# child1.net
KiCad netlist of a schematic drawn in Altium Designer
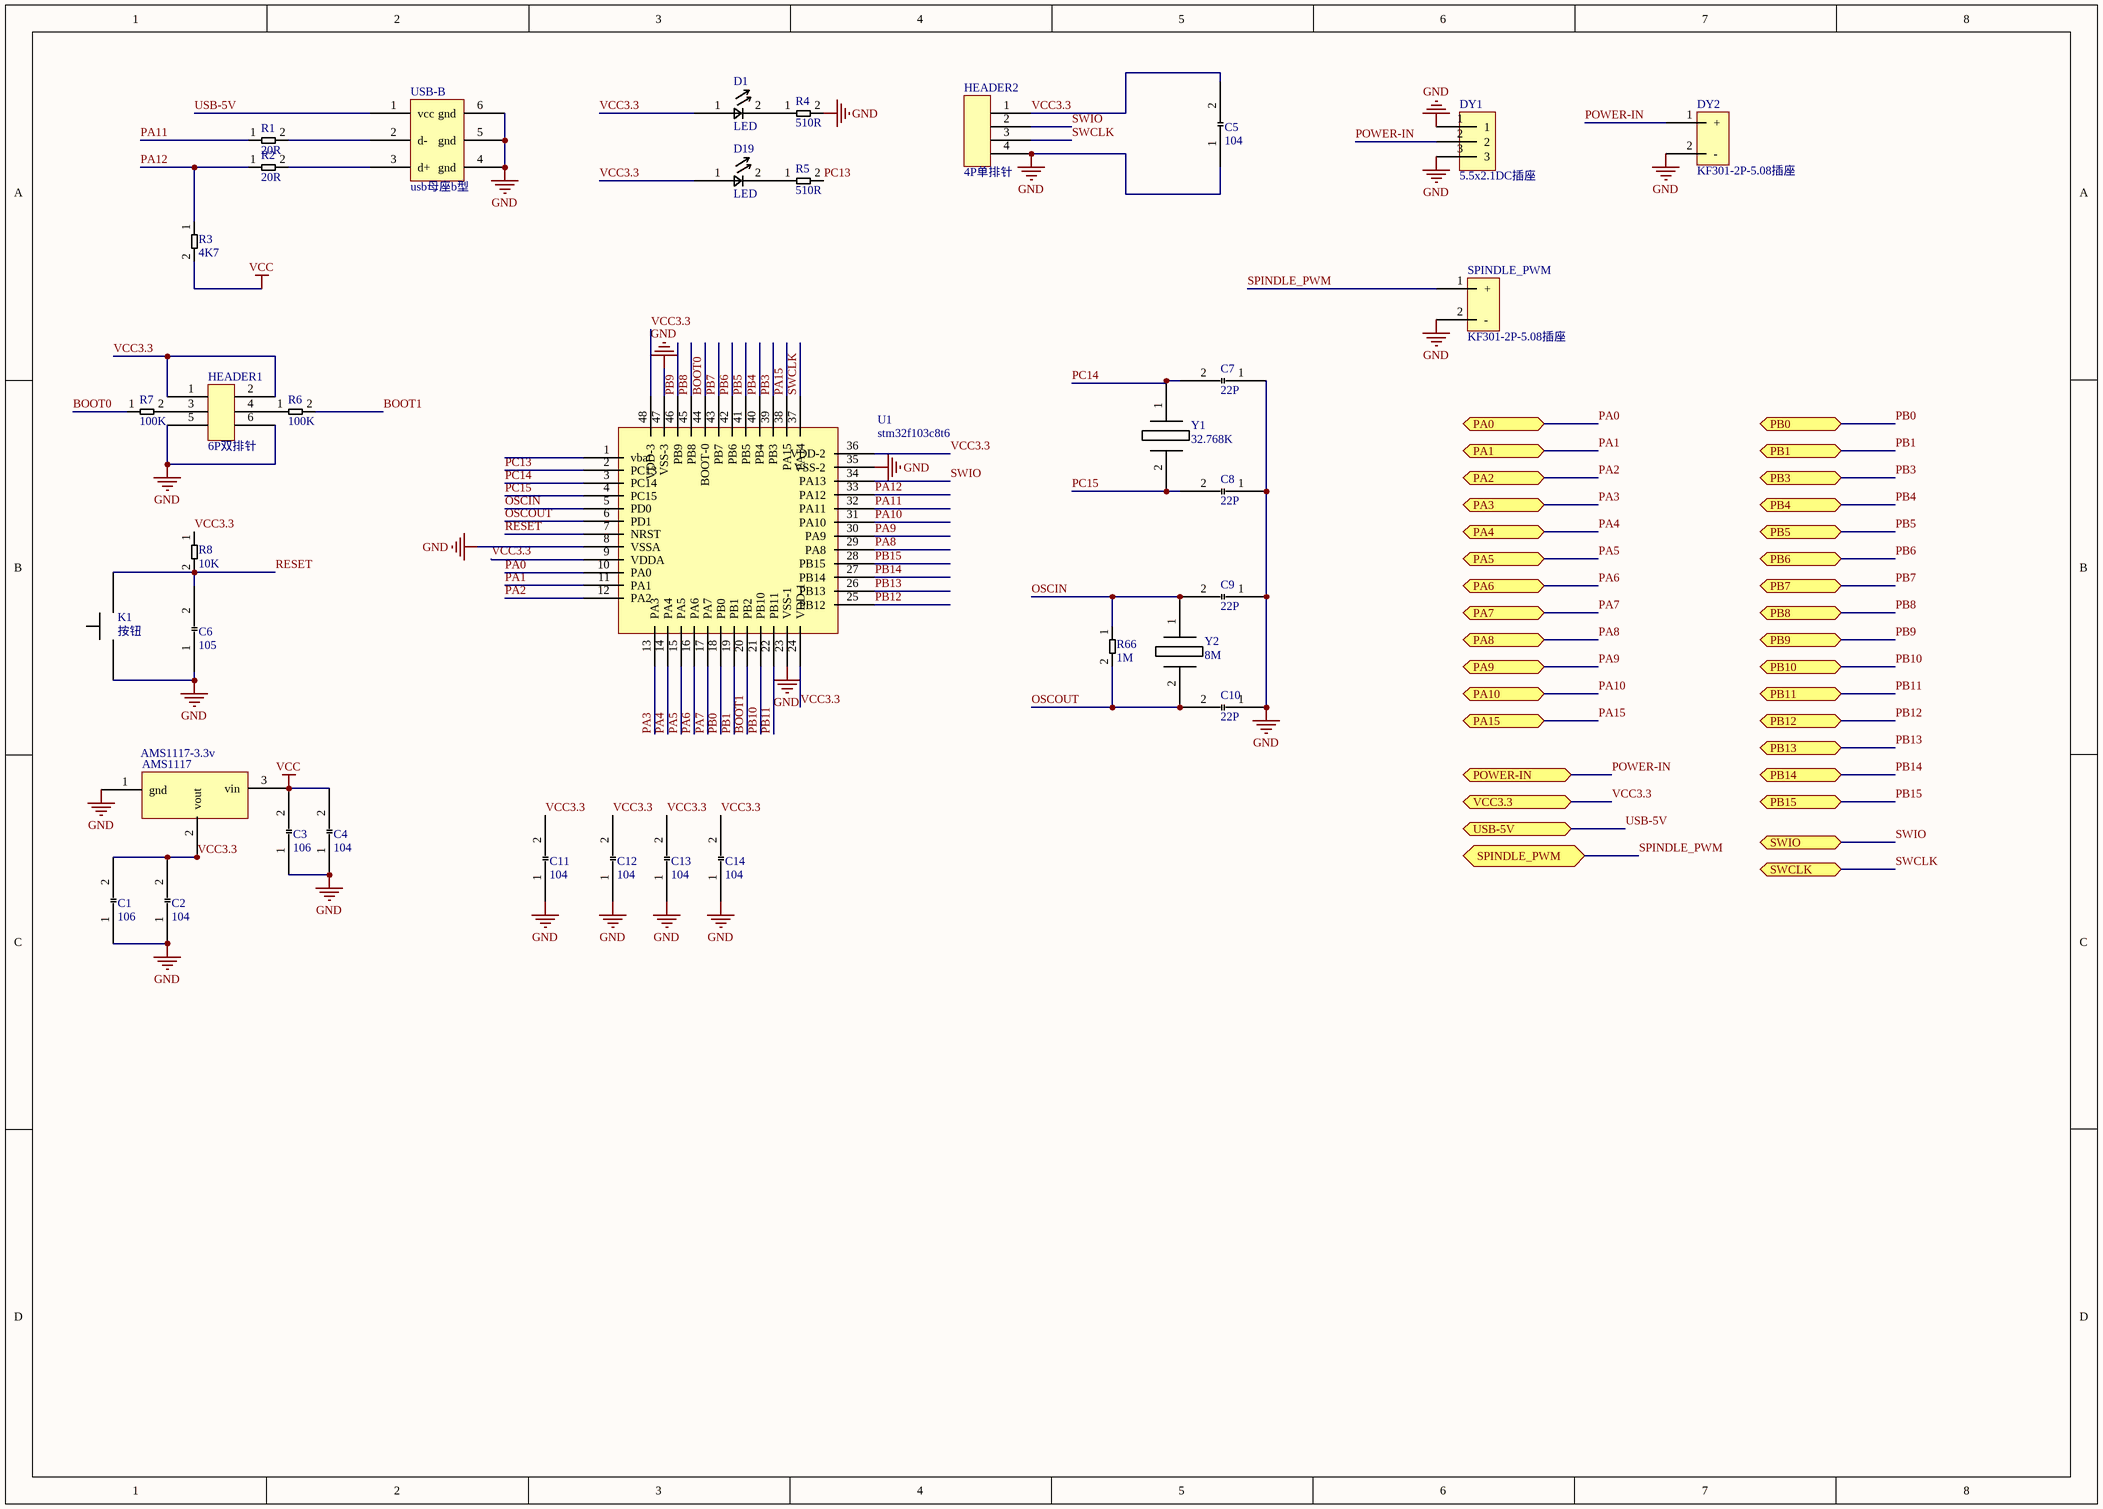
[diagram p0: child1.SchDoc]

(export (version "E")
  (design (tool "Eeschema 10.0.6"))
  (components
    (comp (ref "AMS1117")
      (value "AMS1117-3.3v")
      (footprint "AMS1117-3.3v-sot223")
      (libsource (lib "51单片机") (part "AMS1117-3.3v"))
    )
    (comp (ref "C1") (value "106") (footprint "0805电容") (libsource (lib "51单片机") (part "0805贴片电容")))
    (comp (ref "C2") (value "104") (footprint "0805电容") (libsource (lib "51单片机") (part "0805贴片电容")))
    (comp (ref "C3") (value "106") (footprint "0805电容") (libsource (lib "51单片机") (part "0805贴片电容")))
    (comp (ref "C4") (value "104") (footprint "0805电容") (libsource (lib "51单片机") (part "0805贴片电容")))
    (comp (ref "C5") (value "104") (footprint "0805电容") (libsource (lib "51单片机") (part "0805贴片电容")))
    (comp (ref "C6") (value "105") (footprint "0805电容") (libsource (lib "51单片机") (part "0805贴片电容")))
    (comp (ref "C7") (value "22P") (footprint "0805电容") (libsource (lib "51单片机") (part "0805贴片电容")))
    (comp (ref "C8") (value "22P") (footprint "0805电容") (libsource (lib "51单片机") (part "0805贴片电容")))
    (comp (ref "C9") (value "22P") (footprint "0805电容") (libsource (lib "51单片机") (part "0805贴片电容")))
    (comp (ref "C10") (value "22P") (footprint "0805电容") (libsource (lib "51单片机") (part "0805贴片电容")))
    (comp (ref "C11") (value "104") (footprint "0805电容") (libsource (lib "51单片机") (part "0805贴片电容")))
    (comp (ref "C12") (value "104") (footprint "0805电容") (libsource (lib "51单片机") (part "0805贴片电容")))
    (comp (ref "C13") (value "104") (footprint "0805电容") (libsource (lib "51单片机") (part "0805贴片电容")))
    (comp (ref "C14") (value "104") (footprint "0805电容") (libsource (lib "51单片机") (part "0805贴片电容")))
    (comp (ref "D1") (value "LED") (footprint "0805二极管") (libsource (lib "51单片机") (part "0805贴片发光二极管")))
    (comp (ref "D19") (value "LED") (footprint "0805二极管") (libsource (lib "51单片机") (part "0805贴片发光二极管")))
    (comp (ref "DY1")
      (value "5.5x2.1DC插座")
      (footprint "5.5x2.1DC插座")
      (libsource (lib "51单片机") (part "5.5x2.1DC插座"))
    )
    (comp (ref "DY2")
      (value "KF301-2P-5.08插座")
      (footprint "KF301-2P-5.08插座")
      (libsource (lib "51单片机") (part "KF301-2P-5.08插座"))
    )
    (comp (ref "HEADER1") (value "6P双排针") (footprint "6P双排针") (libsource (lib "51单片机") (part "6P双排针")))
    (comp (ref "HEADER2") (value "4P单排针") (footprint "4p单排针") (libsource (lib "51单片机") (part "4P单排针")))
    (comp (ref "K1") (value "按钮") (footprint "3x4贴片按钮") (libsource (lib "51单片机") (part "3x4贴片按钮")))
    (comp (ref "R1") (value "20R") (footprint "0805电阻") (libsource (lib "51单片机") (part "0805贴片电阻")))
    (comp (ref "R2") (value "20R") (footprint "0805电阻") (libsource (lib "51单片机") (part "0805贴片电阻")))
    (comp (ref "R3") (value "4K7") (footprint "0805电阻") (libsource (lib "51单片机") (part "0805贴片电阻")))
    (comp (ref "R4") (value "510R") (footprint "0805电阻") (libsource (lib "51单片机") (part "0805贴片电阻")))
    (comp (ref "R5") (value "510R") (footprint "0805电阻") (libsource (lib "51单片机") (part "0805贴片电阻")))
    (comp (ref "R6") (value "100K") (footprint "0805电阻") (libsource (lib "51单片机") (part "0805贴片电阻")))
    (comp (ref "R7") (value "100K") (footprint "0805电阻") (libsource (lib "51单片机") (part "0805贴片电阻")))
    (comp (ref "R8") (value "10K") (footprint "0805电阻") (libsource (lib "51单片机") (part "0805贴片电阻")))
    (comp (ref "R66") (value "1M") (footprint "0805电阻") (libsource (lib "51单片机") (part "0805贴片电阻")))
    (comp (ref "SPINDLE_PWM")
      (value "KF301-2P-5.08插座")
      (footprint "KF301-2P-5.08插座")
      (libsource (lib "51单片机") (part "KF301-2P-5.08插座"))
    )
    (comp (ref "U1")
      (value "stm32f103c8t6")
      (footprint "lqfp48")
      (libsource (lib "51单片机") (part "stm32f103c8t6"))
    )
    (comp (ref "USB-B") (value "usb母座b型") (footprint "usb母座b型") (libsource (lib "51单片机") (part "usb母座b型")))
    (comp (ref "Y1") (value "32.768K") (footprint "3.2x1.5晶振") (libsource (lib "51单片机") (part "2脚贴片晶振")))
    (comp (ref "Y2") (value "8M") (footprint "8M贴片晶振") (libsource (lib "51单片机") (part "2脚贴片晶振")))
  )
  (nets
    (net (code "1") (name "/BOOT0") (class "Default")
      (node (ref "R7") (pin "1") (pintype "passive"))
      (node (ref "U1") (pin "44") (pinfunction "BOOT-0_44") (pintype "passive"))
    )
    (net (code "2") (name "/BOOT1") (class "Default")
      (node (ref "R6") (pin "2") (pintype "passive"))
      (node (ref "U1") (pin "20") (pinfunction "PB2_20") (pintype "passive"))
    )
    (net (code "3") (name "/OSCIN") (class "Default")
      (node (ref "C9") (pin "2") (pintype "passive"))
      (node (ref "R66") (pin "1") (pintype "passive"))
      (node (ref "U1") (pin "5") (pinfunction "PD0_5") (pintype "passive"))
      (node (ref "Y2") (pin "1") (pintype "passive"))
    )
    (net (code "4") (name "/OSCOUT") (class "Default")
      (node (ref "C10") (pin "2") (pintype "passive"))
      (node (ref "R66") (pin "2") (pintype "passive"))
      (node (ref "U1") (pin "6") (pinfunction "PD1_6") (pintype "passive"))
      (node (ref "Y2") (pin "2") (pintype "passive"))
    )
    (net (code "5") (name "/PA0") (class "Default")
      (node (ref "U1") (pin "10") (pinfunction "PA0_10") (pintype "passive"))
    )
    (net (code "6") (name "/PA1") (class "Default")
      (node (ref "U1") (pin "11") (pinfunction "PA1_11") (pintype "passive"))
    )
    (net (code "7") (name "/PA2") (class "Default")
      (node (ref "U1") (pin "12") (pinfunction "PA2_12") (pintype "passive"))
    )
    (net (code "8") (name "/PA3") (class "Default")
      (node (ref "U1") (pin "13") (pinfunction "PA3_13") (pintype "passive"))
    )
    (net (code "9") (name "/PA4") (class "Default")
      (node (ref "U1") (pin "14") (pinfunction "PA4_14") (pintype "passive"))
    )
    (net (code "10") (name "/PA5") (class "Default")
      (node (ref "U1") (pin "15") (pinfunction "PA5_15") (pintype "passive"))
    )
    (net (code "11") (name "/PA6") (class "Default")
      (node (ref "U1") (pin "16") (pinfunction "PA6_16") (pintype "passive"))
    )
    (net (code "12") (name "/PA7") (class "Default")
      (node (ref "U1") (pin "17") (pinfunction "PA7_17") (pintype "passive"))
    )
    (net (code "13") (name "/PA8") (class "Default")
      (node (ref "U1") (pin "29") (pinfunction "PA8_29") (pintype "passive"))
    )
    (net (code "14") (name "/PA9") (class "Default")
      (node (ref "U1") (pin "30") (pinfunction "PA9_30") (pintype "passive"))
    )
    (net (code "15") (name "/PA10") (class "Default")
      (node (ref "U1") (pin "31") (pinfunction "PA10_31") (pintype "passive"))
    )
    (net (code "16") (name "/PA11") (class "Default")
      (node (ref "R1") (pin "1") (pintype "passive"))
      (node (ref "U1") (pin "32") (pinfunction "PA11_32") (pintype "passive"))
    )
    (net (code "17") (name "/PA12") (class "Default")
      (node (ref "R2") (pin "1") (pintype "passive"))
      (node (ref "R3") (pin "1") (pintype "passive"))
      (node (ref "U1") (pin "33") (pinfunction "PA12_33") (pintype "passive"))
    )
    (net (code "18") (name "/PA15") (class "Default")
      (node (ref "U1") (pin "38") (pinfunction "PA15_38") (pintype "passive"))
    )
    (net (code "19") (name "/PB0") (class "Default")
      (node (ref "U1") (pin "18") (pinfunction "PB0_18") (pintype "passive"))
    )
    (net (code "20") (name "/PB1") (class "Default")
      (node (ref "U1") (pin "19") (pinfunction "PB1_19") (pintype "passive"))
    )
    (net (code "21") (name "/PB3") (class "Default")
      (node (ref "U1") (pin "39") (pinfunction "PB3_39") (pintype "passive"))
    )
    (net (code "22") (name "/PB4") (class "Default")
      (node (ref "U1") (pin "40") (pinfunction "PB4_40") (pintype "passive"))
    )
    (net (code "23") (name "/PB5") (class "Default")
      (node (ref "U1") (pin "41") (pinfunction "PB5_41") (pintype "passive"))
    )
    (net (code "24") (name "/PB6") (class "Default")
      (node (ref "U1") (pin "42") (pinfunction "PB6_42") (pintype "passive"))
    )
    (net (code "25") (name "/PB7") (class "Default")
      (node (ref "U1") (pin "43") (pinfunction "PB7_43") (pintype "passive"))
    )
    (net (code "26") (name "/PB8") (class "Default")
      (node (ref "U1") (pin "45") (pinfunction "PB8_45") (pintype "passive"))
    )
    (net (code "27") (name "/PB9") (class "Default")
      (node (ref "U1") (pin "46") (pinfunction "PB9_46") (pintype "passive"))
    )
    (net (code "28") (name "/PB10") (class "Default")
      (node (ref "U1") (pin "21") (pinfunction "PB10_21") (pintype "passive"))
    )
    (net (code "29") (name "/PB11") (class "Default")
      (node (ref "U1") (pin "22") (pinfunction "PB11_22") (pintype "passive"))
    )
    (net (code "30") (name "/PB12") (class "Default")
      (node (ref "U1") (pin "25") (pinfunction "PB12_25") (pintype "passive"))
    )
    (net (code "31") (name "/PB13") (class "Default")
      (node (ref "U1") (pin "26") (pinfunction "PB13_26") (pintype "passive"))
    )
    (net (code "32") (name "/PB14") (class "Default")
      (node (ref "U1") (pin "27") (pinfunction "PB14_27") (pintype "passive"))
    )
    (net (code "33") (name "/PB15") (class "Default")
      (node (ref "U1") (pin "28") (pinfunction "PB15_28") (pintype "passive"))
    )
    (net (code "34") (name "/PC13") (class "Default")
      (node (ref "R5") (pin "2") (pintype "passive"))
      (node (ref "U1") (pin "2") (pinfunction "PC13_2") (pintype "passive"))
    )
    (net (code "35") (name "/PC14") (class "Default")
      (node (ref "C7") (pin "2") (pintype "passive"))
      (node (ref "U1") (pin "3") (pinfunction "PC14_3") (pintype "passive"))
      (node (ref "Y1") (pin "1") (pintype "passive"))
    )
    (net (code "36") (name "/PC15") (class "Default")
      (node (ref "C8") (pin "2") (pintype "passive"))
      (node (ref "U1") (pin "4") (pinfunction "PC15_4") (pintype "passive"))
      (node (ref "Y1") (pin "2") (pintype "passive"))
    )
    (net (code "37") (name "/POWER-IN") (class "Default")
      (node (ref "DY1") (pin "2") (pinfunction "2_2") (pintype "passive"))
      (node (ref "DY2") (pin "1") (pinfunction "+_1") (pintype "passive"))
    )
    (net (code "38") (name "/RESET") (class "Default")
      (node (ref "C6") (pin "2") (pintype "passive"))
      (node (ref "K1") (pin "1") (pinfunction "1_1") (pintype "passive"))
      (node (ref "R8") (pin "2") (pintype "passive"))
      (node (ref "U1") (pin "7") (pinfunction "NRST_7") (pintype "passive"))
    )
    (net (code "39") (name "/SPINDLE_PWM") (class "Default")
      (node (ref "SPINDLE_PWM") (pin "1") (pinfunction "+_1") (pintype "passive"))
    )
    (net (code "40") (name "/SWCLK") (class "Default")
      (node (ref "HEADER2") (pin "3") (pintype "passive"))
      (node (ref "U1") (pin "37") (pinfunction "PA14_37") (pintype "passive"))
    )
    (net (code "41") (name "/SWIO") (class "Default")
      (node (ref "HEADER2") (pin "2") (pintype "passive"))
      (node (ref "U1") (pin "34") (pinfunction "PA13_34") (pintype "passive"))
    )
    (net (code "42") (name "/USB-5V") (class "Default")
      (node (ref "USB-B") (pin "1") (pinfunction "vcc_1") (pintype "passive"))
    )
    (net (code "43") (name "/VCC3.3") (class "Default")
      (node (ref "AMS1117") (pin "2") (pinfunction "vout_2") (pintype "passive"))
      (node (ref "C1") (pin "2") (pintype "passive"))
      (node (ref "C11") (pin "2") (pintype "passive"))
      (node (ref "C12") (pin "2") (pintype "passive"))
      (node (ref "C13") (pin "2") (pintype "passive"))
      (node (ref "C14") (pin "2") (pintype "passive"))
      (node (ref "C2") (pin "2") (pintype "passive"))
      (node (ref "C5") (pin "2") (pintype "passive"))
      (node (ref "D1") (pin "1") (pintype "passive"))
      (node (ref "D19") (pin "1") (pintype "passive"))
      (node (ref "HEADER1") (pin "1") (pintype "passive"))
      (node (ref "HEADER1") (pin "2") (pintype "passive"))
      (node (ref "HEADER2") (pin "1") (pintype "passive"))
      (node (ref "R8") (pin "1") (pintype "passive"))
      (node (ref "U1") (pin "24") (pinfunction "VDD-1_24") (pintype "passive"))
      (node (ref "U1") (pin "36") (pinfunction "VDD-2_36") (pintype "passive"))
      (node (ref "U1") (pin "48") (pinfunction "VDD-3_48") (pintype "passive"))
      (node (ref "U1") (pin "9") (pinfunction "VDDA_9") (pintype "passive"))
    )
    (net (code "44") (name "GND") (class "Default")
      (node (ref "AMS1117") (pin "1") (pinfunction "gnd_1") (pintype "passive"))
      (node (ref "C1") (pin "1") (pintype "passive"))
      (node (ref "C10") (pin "1") (pintype "passive"))
      (node (ref "C11") (pin "1") (pintype "passive"))
      (node (ref "C12") (pin "1") (pintype "passive"))
      (node (ref "C13") (pin "1") (pintype "passive"))
      (node (ref "C14") (pin "1") (pintype "passive"))
      (node (ref "C2") (pin "1") (pintype "passive"))
      (node (ref "C3") (pin "1") (pintype "passive"))
      (node (ref "C4") (pin "1") (pintype "passive"))
      (node (ref "C5") (pin "1") (pintype "passive"))
      (node (ref "C6") (pin "1") (pintype "passive"))
      (node (ref "C7") (pin "1") (pintype "passive"))
      (node (ref "C8") (pin "1") (pintype "passive"))
      (node (ref "C9") (pin "1") (pintype "passive"))
      (node (ref "DY1") (pin "1") (pinfunction "1_1") (pintype "passive"))
      (node (ref "DY1") (pin "3") (pinfunction "3_3") (pintype "passive"))
      (node (ref "DY2") (pin "2") (pinfunction "-_2") (pintype "passive"))
      (node (ref "HEADER1") (pin "5") (pintype "passive"))
      (node (ref "HEADER1") (pin "6") (pintype "passive"))
      (node (ref "HEADER2") (pin "4") (pintype "passive"))
      (node (ref "K1") (pin "2") (pinfunction "2_2") (pintype "passive"))
      (node (ref "R4") (pin "2") (pintype "passive"))
      (node (ref "SPINDLE_PWM") (pin "2") (pinfunction "-_2") (pintype "passive"))
      (node (ref "U1") (pin "23") (pinfunction "VSS-1_23") (pintype "passive"))
      (node (ref "U1") (pin "35") (pinfunction "VSS-2_35") (pintype "passive"))
      (node (ref "U1") (pin "47") (pinfunction "VSS-3_47") (pintype "passive"))
      (node (ref "U1") (pin "8") (pinfunction "VSSA_8") (pintype "passive"))
      (node (ref "USB-B") (pin "4") (pinfunction "gnd_4") (pintype "passive"))
      (node (ref "USB-B") (pin "5") (pinfunction "gnd_5") (pintype "passive"))
      (node (ref "USB-B") (pin "6") (pinfunction "gnd_6") (pintype "passive"))
    )
    (net (code "45") (name "Net-(D1-Pad2)") (class "Default")
      (node (ref "D1") (pin "2") (pintype "passive"))
      (node (ref "R4") (pin "1") (pintype "passive"))
    )
    (net (code "46") (name "Net-(D19-Pad2)") (class "Default")
      (node (ref "D19") (pin "2") (pintype "passive"))
      (node (ref "R5") (pin "1") (pintype "passive"))
    )
    (net (code "47") (name "Net-(HEADER1-Pad3)") (class "Default")
      (node (ref "HEADER1") (pin "3") (pintype "passive"))
      (node (ref "R7") (pin "2") (pintype "passive"))
    )
    (net (code "48") (name "Net-(HEADER1-Pad4)") (class "Default")
      (node (ref "HEADER1") (pin "4") (pintype "passive"))
      (node (ref "R6") (pin "1") (pintype "passive"))
    )
    (net (code "49") (name "Net-(USB-B-d+)") (class "Default")
      (node (ref "R2") (pin "2") (pintype "passive"))
      (node (ref "USB-B") (pin "3") (pinfunction "d+_3") (pintype "passive"))
    )
    (net (code "50") (name "Net-(USB-B-d-)") (class "Default")
      (node (ref "R1") (pin "2") (pintype "passive"))
      (node (ref "USB-B") (pin "2") (pinfunction "d-_2") (pintype "passive"))
    )
    (net (code "51") (name "VCC") (class "Default")
      (node (ref "AMS1117") (pin "3") (pinfunction "vin_3") (pintype "passive"))
      (node (ref "C3") (pin "2") (pintype "passive"))
      (node (ref "C4") (pin "2") (pintype "passive"))
      (node (ref "R3") (pin "2") (pintype "passive"))
    )
    (net (code "52") (name "unconnected-(U1-vbat-Pad1)") (class "Default")
      (node (ref "U1") (pin "1") (pinfunction "vbat_1") (pintype "passive"))
    )
  )
)
